# Addon-LAN-WLAN-without-MAPLE_or-OneWire_.net
KiCad netlist of a schematic drawn in EAGLE
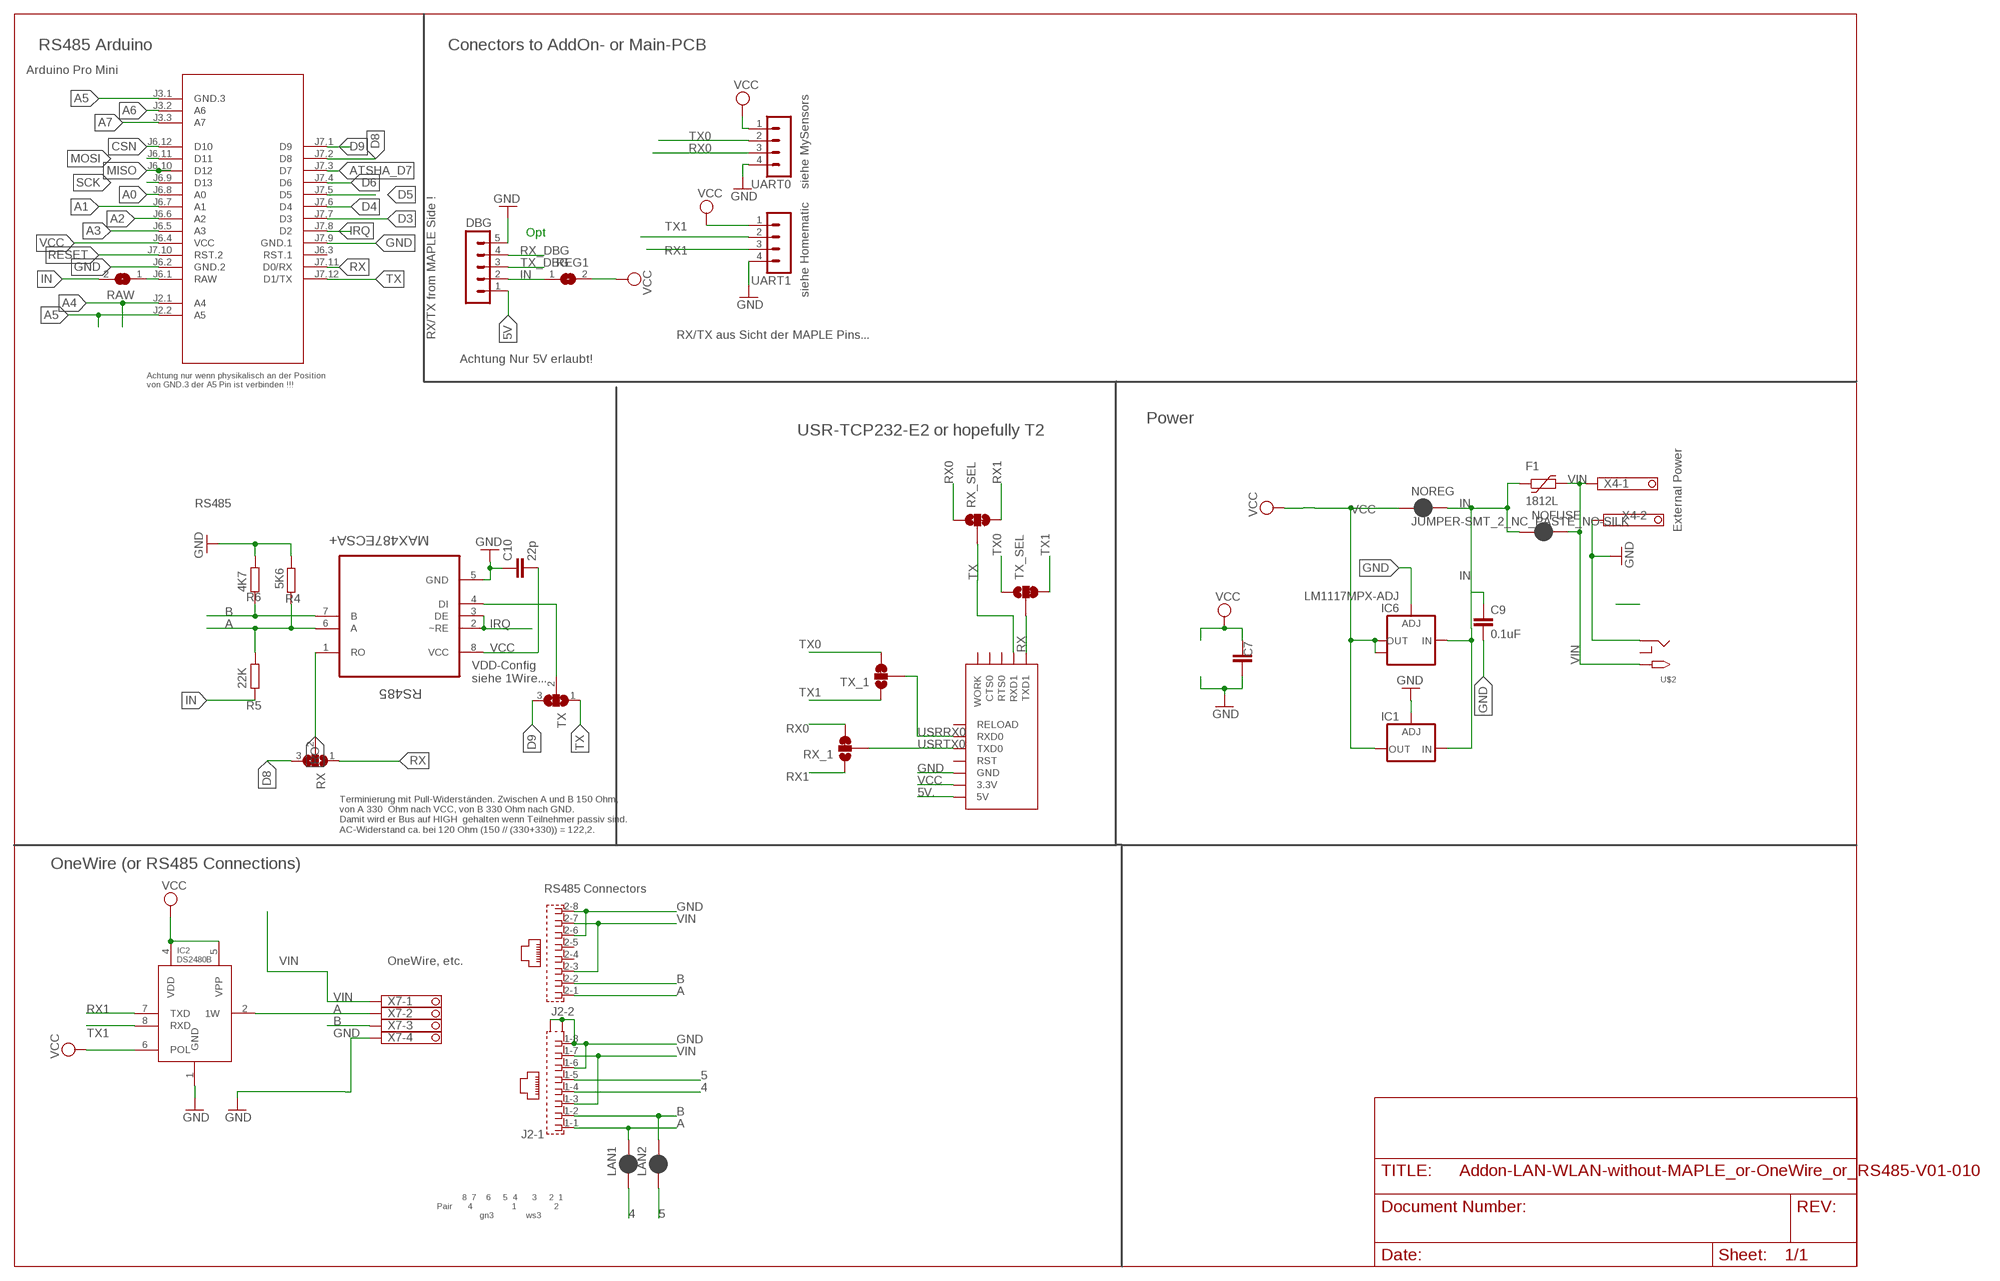
[diagram p0: schematic, sheet 1]

(export (version "E")
  (design (tool "Eeschema 10.0.6"))
  (components
    (comp (ref "C7")
      (value "C-EUC1812")
      (footprint "eagle-import:C1812")
      (libsource (lib "eagle-import") (part "rcl_334_C-EUC1812"))
    )
    (comp (ref "C9")
      (value "0.1uF")
      (footprint "eagle-import:C1206")
      (libsource (lib "eagle-import") (part "rcl_334_C-EUC1206"))
    )
    (comp (ref "C10")
      (value "22p")
      (footprint "eagle-import:C0805")
      (libsource (lib "eagle-import") (part "C-EUC0805"))
    )
    (comp (ref "DBG")
      (value "MA05-1")
      (footprint "eagle-import:MA05-1")
      (libsource (lib "eagle-import") (part "MA05-1"))
    )
    (comp (ref "F1")
      (value "1812L")
      (footprint "eagle-import:1812L")
      (libsource (lib "eagle-import") (part "1812L"))
    )
    (comp (ref "IC1")
      (value "LD117ADT50TR")
      (footprint "eagle-import:DPACK")
      (libsource (lib "eagle-import") (part "LD117A?DT50TR"))
    )
    (comp (ref "IC2")
      (value "DS2480B")
      (footprint "eagle-import:SO08")
      (libsource (lib "eagle-import") (part "DS2480B"))
    )
    (comp (ref "IC6")
      (value "LM1117MPX-ADJ")
      (footprint "eagle-import:SOT223")
      (libsource (lib "eagle-import") (part "LM1117MPX-ADJ"))
    )
    (comp (ref "J2")
      (value "RJ45_2X_S")
      (footprint "eagle-import:RJ45_2X_S")
      (libsource (lib "eagle-import") (part "RJ45_2X_S"))
    )
    (comp (ref "LAN1")
      (value "JUMPER-SMT_2_NC_PASTE_SILK")
      (footprint "eagle-import:SMT-JUMPER_2_NC_PASTE_SILK")
      (libsource (lib "eagle-import") (part "JUMPER-SMT_2_NC_PASTE_SILK"))
    )
    (comp (ref "LAN2")
      (value "JUMPER-SMT_2_NC_PASTE_SILK")
      (footprint "eagle-import:SMT-JUMPER_2_NC_PASTE_SILK")
      (libsource (lib "eagle-import") (part "JUMPER-SMT_2_NC_PASTE_SILK"))
    )
    (comp (ref "M1")
      (value "ARDUINO-PRO-MINI-3.3V#NP")
      (footprint "eagle-import:ARDUINO-PRO-MINI#NP")
      (libsource (lib "eagle-import") (part "ARDUINO-PRO-MINI-#NP3.3V"))
    )
    (comp (ref "NOFUSE")
      (value "JUMPER-SMT_2_NC_PASTE_NO-SILK")
      (footprint "eagle-import:SMT-JUMPER_2_NC_PASTE_NO-SILK")
      (libsource (lib "eagle-import") (part "JUMPER-SMT_2_NC_PASTE_NO-SILK"))
    )
    (comp (ref "NOREG")
      (value "JUMPER-SMT_2_NC_PASTE_NO-SILK")
      (footprint "eagle-import:SMT-JUMPER_2_NC_PASTE_NO-SILK")
      (libsource (lib "eagle-import") (part "SparkFun-Jumpers_528_JUMPER-SMT_2_NC_PASTE_NO-SILK"))
    )
    (comp (ref "R4")
      (value "5K6")
      (footprint "eagle-import:R0805")
      (libsource (lib "eagle-import") (part "R-EU_R0805"))
    )
    (comp (ref "R5")
      (value "22K")
      (footprint "eagle-import:R0805")
      (libsource (lib "eagle-import") (part "R-EU_R0805"))
    )
    (comp (ref "R6")
      (value "4K7")
      (footprint "eagle-import:R0805")
      (libsource (lib "eagle-import") (part "R-EU_R0805"))
    )
    (comp (ref "RAW") (value "SJ") (footprint "eagle-import:SJ") (libsource (lib "eagle-import") (part "SJ")))
    (comp (ref "REG1")
      (value "SJ")
      (footprint "eagle-import:SJ")
      (libsource (lib "eagle-import") (part "jumper_252_SJ"))
    )
    (comp (ref "RS485")
      (value "MAX487ECSA+")
      (footprint "eagle-import:SOIC127P600X175-8N")
      (libsource (lib "eagle-import") (part "MAX487ECSA+"))
    )
    (comp (ref "RX")
      (value "SJ2W")
      (footprint "eagle-import:SJ_2")
      (libsource (lib "eagle-import") (part "SJ2W"))
    )
    (comp (ref "RX_1")
      (value "JUMPER-SMT_3_1-NC_TRACE_SILK")
      (footprint "eagle-import:SMT-JUMPER_3_1-NC_TRACE_SILK")
      (libsource (lib "eagle-import") (part "JUMPER-SMT_3_1-NC_TRACE_SILK"))
    )
    (comp (ref "RX_SEL")
      (value "JUMPER-SMT_3_1-NC_TRACE_SILK")
      (footprint "eagle-import:SMT-JUMPER_3_1-NC_TRACE_SILK")
      (libsource (lib "eagle-import") (part "JUMPER-SMT_3_1-NC_TRACE_SILK"))
    )
    (comp (ref "TX")
      (value "SJ2W")
      (footprint "eagle-import:SJ_2")
      (libsource (lib "eagle-import") (part "SJ2W"))
    )
    (comp (ref "TX_1")
      (value "JUMPER-SMT_3_1-NC_TRACE_SILK")
      (footprint "eagle-import:SMT-JUMPER_3_1-NC_TRACE_SILK")
      (libsource (lib "eagle-import") (part "JUMPER-SMT_3_1-NC_TRACE_SILK"))
    )
    (comp (ref "TX_SEL")
      (value "JUMPER-SMT_3_1-NC_TRACE_SILK")
      (footprint "eagle-import:SMT-JUMPER_3_1-NC_TRACE_SILK")
      (libsource (lib "eagle-import") (part "JUMPER-SMT_3_1-NC_TRACE_SILK"))
    )
    (comp (ref "U$2")
      (value "2.1MMJACKTHM")
      (footprint "eagle-import:PJ-102A")
      (libsource (lib "eagle-import") (part "2.1MMJACKTHM"))
    )
    (comp (ref "U$5")
      (value "USR-TCP232-E2")
      (footprint "eagle-import:USR-TCP232-E2")
      (libsource (lib "eagle-import") (part "USR-TCP232-E2"))
    )
    (comp (ref "UART0")
      (value "MA04-1")
      (footprint "eagle-import:MA04-1")
      (libsource (lib "eagle-import") (part "MA04-1"))
    )
    (comp (ref "UART1")
      (value "MA04-1")
      (footprint "eagle-import:MA04-1")
      (libsource (lib "eagle-import") (part "MA04-1"))
    )
    (comp (ref "X4")
      (value "1751248")
      (footprint "eagle-import:1751248")
      (libsource (lib "eagle-import") (part "1751248"))
    )
    (comp (ref "X7")
      (value "1751264")
      (footprint "eagle-import:1751264")
      (libsource (lib "eagle-import") (part "1751264"))
    )
  )
  (nets
    (net (code "1") (name "/4") (class "Default")
      (node (ref "J2") (pin "1-4") (pinfunction "4_1-4") (pintype "passive"))
      (node (ref "LAN1") (pin "1") (pinfunction "1_1") (pintype "passive"))
    )
    (net (code "2") (name "/5") (class "Default")
      (node (ref "J2") (pin "1-5") (pinfunction "5_1-5") (pintype "passive"))
      (node (ref "LAN2") (pin "1") (pinfunction "1_1") (pintype "passive"))
    )
    (net (code "3") (name "/5V.") (class "Default")
      (node (ref "U$5") (pin "5V") (pinfunction "5V_5V") (pintype "bidirectional"))
    )
    (net (code "4") (name "/A") (class "Default")
      (node (ref "IC2") (pin "2") (pinfunction "1W_2") (pintype "open_collector"))
      (node (ref "J2") (pin "1-1") (pinfunction "1_1-1") (pintype "passive"))
      (node (ref "J2") (pin "2-1") (pinfunction "1_2-1") (pintype "passive"))
      (node (ref "LAN1") (pin "2") (pinfunction "2_2") (pintype "passive"))
      (node (ref "R4") (pin "2") (pinfunction "2_2") (pintype "passive"))
      (node (ref "R5") (pin "2") (pinfunction "2_2") (pintype "passive"))
      (node (ref "RS485") (pin "6") (pinfunction "A_6") (pintype "bidirectional"))
      (node (ref "X7") (pin "2") (pinfunction "K_2") (pintype "passive"))
    )
    (net (code "5") (name "/B") (class "Default")
      (node (ref "J2") (pin "1-2") (pinfunction "2_1-2") (pintype "passive"))
      (node (ref "J2") (pin "2-2") (pinfunction "2_2-2") (pintype "passive"))
      (node (ref "LAN2") (pin "2") (pinfunction "2_2") (pintype "passive"))
      (node (ref "R6") (pin "1") (pinfunction "1_1") (pintype "passive"))
      (node (ref "RS485") (pin "7") (pinfunction "B_7") (pintype "bidirectional"))
      (node (ref "X7") (pin "3") (pinfunction "K_3") (pintype "passive"))
    )
    (net (code "6") (name "/RX0") (class "Default")
      (node (ref "RX_1") (pin "3") (pinfunction "3_3") (pintype "passive"))
      (node (ref "RX_SEL") (pin "1") (pinfunction "1_1") (pintype "passive"))
      (node (ref "UART0") (pin "3") (pinfunction "3_3") (pintype "passive"))
    )
    (net (code "7") (name "/RX1") (class "Default")
      (node (ref "IC2") (pin "7") (pinfunction "TXD_7") (pintype "input"))
      (node (ref "RX_1") (pin "1") (pinfunction "1_1") (pintype "passive"))
      (node (ref "RX_SEL") (pin "3") (pinfunction "3_3") (pintype "passive"))
      (node (ref "UART1") (pin "3") (pinfunction "3_3") (pintype "passive"))
    )
    (net (code "8") (name "/RX_DBG") (class "Default")
      (node (ref "DBG") (pin "4") (pinfunction "4_4") (pintype "passive"))
    )
    (net (code "9") (name "/TX0") (class "Default")
      (node (ref "TX_1") (pin "3") (pinfunction "3_3") (pintype "passive"))
      (node (ref "TX_SEL") (pin "1") (pinfunction "1_1") (pintype "passive"))
      (node (ref "UART0") (pin "2") (pinfunction "2_2") (pintype "passive"))
    )
    (net (code "10") (name "/TX1") (class "Default")
      (node (ref "IC2") (pin "8") (pinfunction "RXD_8") (pintype "output"))
      (node (ref "TX_1") (pin "1") (pinfunction "1_1") (pintype "passive"))
      (node (ref "TX_SEL") (pin "3") (pinfunction "3_3") (pintype "passive"))
      (node (ref "UART1") (pin "2") (pinfunction "2_2") (pintype "passive"))
    )
    (net (code "11") (name "/TX_DBG") (class "Default")
      (node (ref "DBG") (pin "3") (pinfunction "3_3") (pintype "passive"))
    )
    (net (code "12") (name "/USRRX0") (class "Default")
      (node (ref "TX_1") (pin "2") (pinfunction "2_2") (pintype "passive"))
      (node (ref "U$5") (pin "RXD0") (pinfunction "RXD0_RXD0") (pintype "input"))
    )
    (net (code "13") (name "/USRTX0") (class "Default")
      (node (ref "RX_1") (pin "2") (pinfunction "2_2") (pintype "passive"))
      (node (ref "U$5") (pin "TXD0") (pinfunction "TXD0_TXD0") (pintype "output"))
    )
    (net (code "14") (name "/VIN") (class "Default")
      (node (ref "F1") (pin "P$2") (pinfunction "2_P$2") (pintype "passive"))
      (node (ref "J2") (pin "1-3") (pinfunction "3_1-3") (pintype "passive"))
      (node (ref "J2") (pin "1-7") (pinfunction "7_1-7") (pintype "passive"))
      (node (ref "J2") (pin "2-3") (pinfunction "3_2-3") (pintype "passive"))
      (node (ref "J2") (pin "2-7") (pinfunction "7_2-7") (pintype "passive"))
      (node (ref "NOFUSE") (pin "2") (pinfunction "2_2") (pintype "passive"))
      (node (ref "U$2") (pin "TIP") (pinfunction "TIP_TIP") (pintype "bidirectional"))
      (node (ref "X4") (pin "1") (pinfunction "K_1") (pintype "passive"))
      (node (ref "X7") (pin "1") (pinfunction "K_1") (pintype "passive"))
    )
    (net (code "15") (name "5V") (class "Default")
      (node (ref "DBG") (pin "1") (pinfunction "1_1") (pintype "passive"))
    )
    (net (code "16") (name "A0") (class "Default")
      (node (ref "M1") (pin "J6.8") (pinfunction "A0_J6.8") (pintype "bidirectional"))
    )
    (net (code "17") (name "A1") (class "Default")
      (node (ref "M1") (pin "J6.7") (pinfunction "A1_J6.7") (pintype "bidirectional"))
    )
    (net (code "18") (name "A2") (class "Default")
      (node (ref "M1") (pin "J6.6") (pinfunction "A2_J6.6") (pintype "bidirectional"))
    )
    (net (code "19") (name "A3") (class "Default")
      (node (ref "M1") (pin "J6.5") (pinfunction "A3_J6.5") (pintype "bidirectional"))
    )
    (net (code "20") (name "A4") (class "Default")
      (node (ref "M1") (pin "J2.1") (pinfunction "A4_J2.1") (pintype "bidirectional"))
    )
    (net (code "21") (name "A5") (class "Default")
      (node (ref "M1") (pin "J2.2") (pinfunction "A5_J2.2") (pintype "bidirectional"))
      (node (ref "M1") (pin "J3.1") (pinfunction "GND.3_J3.1") (pintype "bidirectional"))
    )
    (net (code "22") (name "A6") (class "Default")
      (node (ref "M1") (pin "J3.2") (pinfunction "A6_J3.2") (pintype "bidirectional"))
    )
    (net (code "23") (name "A7") (class "Default")
      (node (ref "M1") (pin "J3.3") (pinfunction "A7_J3.3") (pintype "bidirectional"))
    )
    (net (code "24") (name "ATSHA_D7") (class "Default")
      (node (ref "M1") (pin "J7.3") (pinfunction "D7_J7.3") (pintype "bidirectional"))
    )
    (net (code "25") (name "CSN") (class "Default")
      (node (ref "M1") (pin "J6.12") (pinfunction "D10_J6.12") (pintype "bidirectional"))
    )
    (net (code "26") (name "D3") (class "Default")
      (node (ref "M1") (pin "J7.7") (pinfunction "D3_J7.7") (pintype "bidirectional"))
    )
    (net (code "27") (name "D4") (class "Default")
      (node (ref "M1") (pin "J7.6") (pinfunction "D4_J7.6") (pintype "bidirectional"))
    )
    (net (code "28") (name "D5") (class "Default")
      (node (ref "M1") (pin "J7.5") (pinfunction "D5_J7.5") (pintype "bidirectional"))
    )
    (net (code "29") (name "D6") (class "Default")
      (node (ref "M1") (pin "J7.4") (pinfunction "D6_J7.4") (pintype "bidirectional"))
    )
    (net (code "30") (name "D8") (class "Default")
      (node (ref "M1") (pin "J7.2") (pinfunction "D8_J7.2") (pintype "bidirectional"))
      (node (ref "RX") (pin "3") (pinfunction "3_3") (pintype "passive"))
    )
    (net (code "31") (name "D9") (class "Default")
      (node (ref "M1") (pin "J7.1") (pinfunction "D9_J7.1") (pintype "bidirectional"))
      (node (ref "TX") (pin "3") (pinfunction "3_3") (pintype "passive"))
    )
    (net (code "32") (name "GND") (class "Default")
      (node (ref "C10") (pin "1") (pinfunction "1_1") (pintype "passive"))
      (node (ref "C7") (pin "1") (pinfunction "1_1") (pintype "passive"))
      (node (ref "C9") (pin "2") (pinfunction "2_2") (pintype "passive"))
      (node (ref "DBG") (pin "5") (pinfunction "5_5") (pintype "passive"))
      (node (ref "IC1") (pin "1") (pinfunction "ADJ_1") (pintype "input"))
      (node (ref "IC2") (pin "1") (pinfunction "GND_1") (pintype "power_in"))
      (node (ref "IC6") (pin "1") (pinfunction "ADJ_1") (pintype "input"))
      (node (ref "J2") (pin "1-6") (pinfunction "6_1-6") (pintype "passive"))
      (node (ref "J2") (pin "1-8") (pinfunction "8_1-8") (pintype "passive"))
      (node (ref "J2") (pin "2-6") (pinfunction "6_2-6") (pintype "passive"))
      (node (ref "J2") (pin "2-8") (pinfunction "8_2-8") (pintype "passive"))
      (node (ref "J2") (pin "G1") (pinfunction "S2_G1") (pintype "passive"))
      (node (ref "J2") (pin "G3") (pinfunction "S1_G3") (pintype "passive"))
      (node (ref "M1") (pin "J6.2") (pinfunction "GND.2_J6.2") (pintype "power_in"))
      (node (ref "M1") (pin "J7.9") (pinfunction "GND.1_J7.9") (pintype "power_in"))
      (node (ref "R4") (pin "1") (pinfunction "1_1") (pintype "passive"))
      (node (ref "R6") (pin "2") (pinfunction "2_2") (pintype "passive"))
      (node (ref "RS485") (pin "5") (pinfunction "GND_5") (pintype "passive"))
      (node (ref "U$2") (pin "RING") (pinfunction "RING_RING") (pintype "bidirectional"))
      (node (ref "U$5") (pin "GND") (pinfunction "GND_GND") (pintype "bidirectional"))
      (node (ref "UART0") (pin "4") (pinfunction "4_4") (pintype "passive"))
      (node (ref "UART1") (pin "4") (pinfunction "4_4") (pintype "passive"))
      (node (ref "X4") (pin "2") (pinfunction "K_2") (pintype "passive"))
      (node (ref "X7") (pin "4") (pinfunction "K_4") (pintype "passive"))
    )
    (net (code "33") (name "IN") (class "Default")
      (node (ref "C9") (pin "1") (pinfunction "1_1") (pintype "passive"))
      (node (ref "DBG") (pin "2") (pinfunction "2_2") (pintype "passive"))
      (node (ref "F1") (pin "P$1") (pinfunction "1_P$1") (pintype "passive"))
      (node (ref "IC1") (pin "3") (pinfunction "IN_3") (pintype "input"))
      (node (ref "IC6") (pin "3") (pinfunction "IN_3") (pintype "input"))
      (node (ref "NOFUSE") (pin "1") (pinfunction "1_1") (pintype "passive"))
      (node (ref "NOREG") (pin "2") (pinfunction "2_2") (pintype "passive"))
      (node (ref "R5") (pin "1") (pinfunction "1_1") (pintype "passive"))
      (node (ref "RAW") (pin "2") (pinfunction "2_2") (pintype "passive"))
      (node (ref "REG1") (pin "1") (pinfunction "1_1") (pintype "passive"))
    )
    (net (code "34") (name "IRQ") (class "Default")
      (node (ref "M1") (pin "J7.8") (pinfunction "D2_J7.8") (pintype "bidirectional"))
      (node (ref "RS485") (pin "2") (pinfunction "~{RE}_2") (pintype "input"))
      (node (ref "RS485") (pin "3") (pinfunction "DE_3") (pintype "input"))
    )
    (net (code "35") (name "MISO") (class "Default")
      (node (ref "M1") (pin "J6.10") (pinfunction "D12_J6.10") (pintype "bidirectional"))
    )
    (net (code "36") (name "MOSI") (class "Default")
      (node (ref "M1") (pin "J6.11") (pinfunction "D11_J6.11") (pintype "bidirectional"))
    )
    (net (code "37") (name "Net-(M1-RAW)") (class "Default")
      (node (ref "M1") (pin "J6.1") (pinfunction "RAW_J6.1") (pintype "power_in"))
      (node (ref "RAW") (pin "1") (pinfunction "1_1") (pintype "passive"))
    )
    (net (code "38") (name "Net-(RS485-DI)") (class "Default")
      (node (ref "RS485") (pin "4") (pinfunction "DI_4") (pintype "input"))
      (node (ref "TX") (pin "2") (pinfunction "2_2") (pintype "passive"))
    )
    (net (code "39") (name "RESET") (class "Default")
      (node (ref "M1") (pin "J7.10") (pinfunction "RST.2_J7.10") (pintype "bidirectional"))
    )
    (net (code "40") (name "RO") (class "Default")
      (node (ref "RS485") (pin "1") (pinfunction "RO_1") (pintype "output"))
      (node (ref "RX") (pin "2") (pinfunction "2_2") (pintype "passive"))
    )
    (net (code "41") (name "RX") (class "Default")
      (node (ref "M1") (pin "J7.11") (pinfunction "D0/RX_J7.11") (pintype "bidirectional"))
      (node (ref "RX") (pin "1") (pinfunction "1_1") (pintype "passive"))
      (node (ref "TX_SEL") (pin "2") (pinfunction "2_2") (pintype "passive"))
      (node (ref "U$5") (pin "TXD1") (pinfunction "TXD1_TXD1") (pintype "output"))
    )
    (net (code "42") (name "SCK") (class "Default")
      (node (ref "M1") (pin "J6.9") (pinfunction "D13_J6.9") (pintype "bidirectional"))
    )
    (net (code "43") (name "TX") (class "Default")
      (node (ref "M1") (pin "J7.12") (pinfunction "D1/TX_J7.12") (pintype "bidirectional"))
      (node (ref "RX_SEL") (pin "2") (pinfunction "2_2") (pintype "passive"))
      (node (ref "TX") (pin "1") (pinfunction "1_1") (pintype "passive"))
      (node (ref "U$5") (pin "RXD1") (pinfunction "RXD1_RXD1") (pintype "input"))
    )
    (net (code "44") (name "VCC") (class "Default")
      (node (ref "C10") (pin "2") (pinfunction "2_2") (pintype "passive"))
      (node (ref "C7") (pin "2") (pinfunction "2_2") (pintype "passive"))
      (node (ref "IC1") (pin "4") (pinfunction "OUT_4") (pintype "passive"))
      (node (ref "IC2") (pin "4") (pinfunction "VDD_4") (pintype "power_in"))
      (node (ref "IC2") (pin "5") (pinfunction "VPP_5") (pintype "power_in"))
      (node (ref "IC2") (pin "6") (pinfunction "POL_6") (pintype "input"))
      (node (ref "IC6") (pin "2") (pinfunction "OUT_2") (pintype "passive"))
      (node (ref "IC6") (pin "TAB") (pinfunction "OUT1_TAB") (pintype "passive"))
      (node (ref "M1") (pin "J6.4") (pinfunction "VCC_J6.4") (pintype "power_in"))
      (node (ref "NOREG") (pin "1") (pinfunction "1_1") (pintype "passive"))
      (node (ref "REG1") (pin "2") (pinfunction "2_2") (pintype "passive"))
      (node (ref "RS485") (pin "8") (pinfunction "VCC_8") (pintype "power_in"))
      (node (ref "U$5") (pin "3.3V") (pinfunction "3.3V_3.3V") (pintype "bidirectional"))
      (node (ref "UART0") (pin "1") (pinfunction "1_1") (pintype "passive"))
      (node (ref "UART1") (pin "1") (pinfunction "1_1") (pintype "passive"))
    )
    (net (code "45") (name "unconnected-(J2B-4-Pad2-4)") (class "Default")
      (node (ref "J2") (pin "2-4") (pinfunction "4_2-4") (pintype "passive"))
    )
    (net (code "46") (name "unconnected-(J2B-5-Pad2-5)") (class "Default")
      (node (ref "J2") (pin "2-5") (pinfunction "5_2-5") (pintype "passive"))
    )
    (net (code "47") (name "unconnected-(M1-RST.1-PadJ6.3)") (class "Default")
      (node (ref "M1") (pin "J6.3") (pinfunction "RST.1_J6.3") (pintype "bidirectional"))
    )
    (net (code "48") (name "unconnected-(U$2-PadRING_SW)") (class "Default")
      (node (ref "U$2") (pin "RING_SW") (pinfunction "RING_SW_RING_SW") (pintype "bidirectional"))
    )
    (net (code "49") (name "unconnected-(U$5-PadCTS0)") (class "Default")
      (node (ref "U$5") (pin "CTS0") (pinfunction "CTS0_CTS0") (pintype "bidirectional"))
    )
    (net (code "50") (name "unconnected-(U$5-PadRELOAD)") (class "Default")
      (node (ref "U$5") (pin "RELOAD") (pinfunction "RELOAD_RELOAD") (pintype "bidirectional"))
    )
    (net (code "51") (name "unconnected-(U$5-PadRST)") (class "Default")
      (node (ref "U$5") (pin "RST") (pinfunction "RST_RST") (pintype "bidirectional"))
    )
    (net (code "52") (name "unconnected-(U$5-PadRTS0)") (class "Default")
      (node (ref "U$5") (pin "RTS0") (pinfunction "RTS0_RTS0") (pintype "bidirectional"))
    )
    (net (code "53") (name "unconnected-(U$5-PadWORK)") (class "Default")
      (node (ref "U$5") (pin "WORK") (pinfunction "WORK_WORK") (pintype "bidirectional"))
    )
  )
)
